# touch_controller.net
KiCad netlist of a schematic drawn in EAGLE
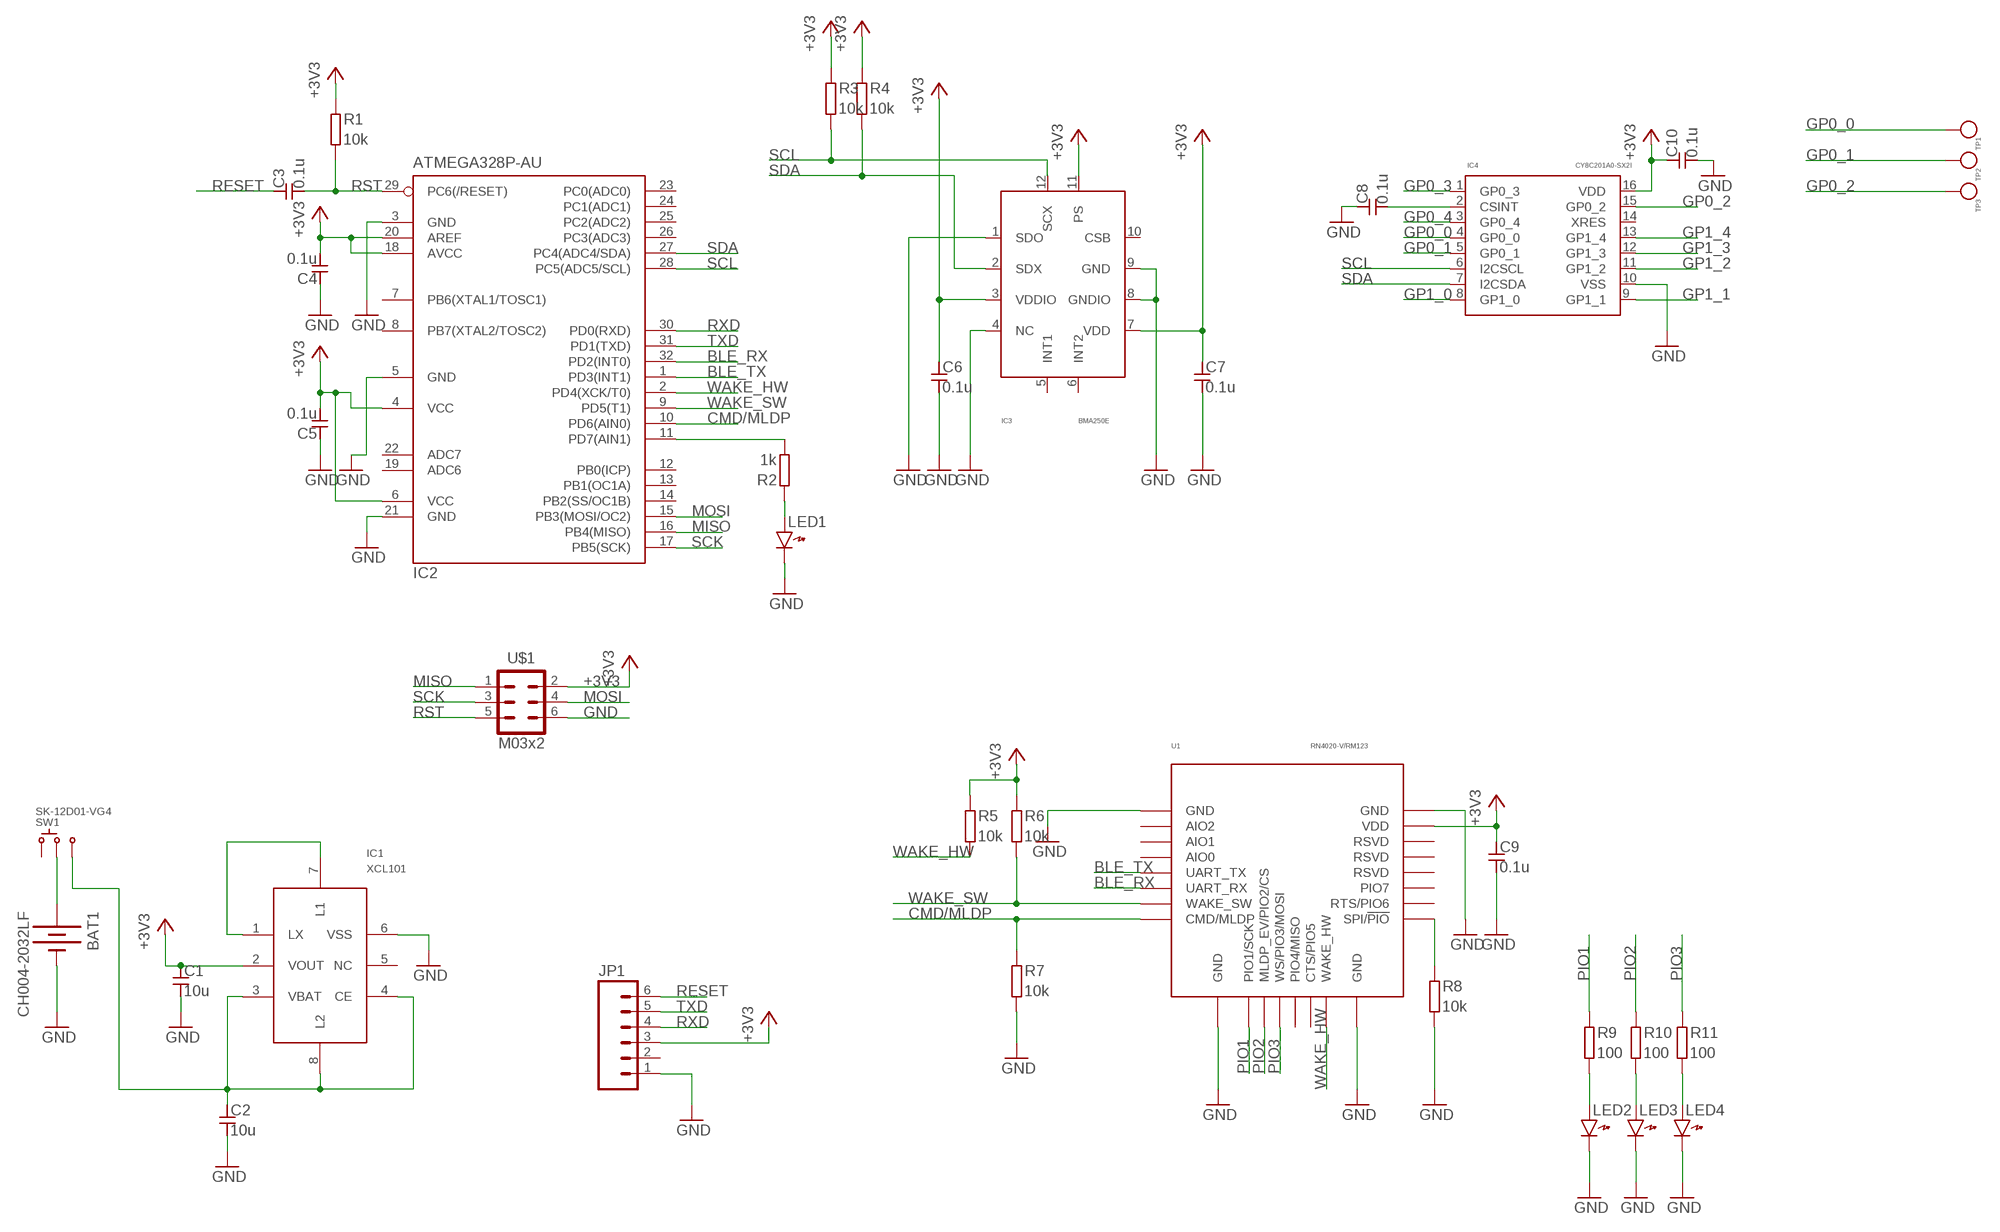
[diagram p0: schematic, sheet 1]

(export (version "E")
  (design (tool "Eeschema 10.0.6"))
  (components
    (comp (ref "BAT1")
      (value "CH004-2032LF")
      (footprint "eagle-import:CH004-2032LF")
      (libsource (lib "eagle-import") (part "CH004-2032LF"))
    )
    (comp (ref "C1")
      (value "10u")
      (footprint "eagle-import:SMD2012_REDUCED")
      (libsource (lib "eagle-import") (part "CAPACITOR2012_REDUCED"))
    )
    (comp (ref "C2")
      (value "10u")
      (footprint "eagle-import:SMD2012_REDUCED")
      (libsource (lib "eagle-import") (part "CAPACITOR2012_REDUCED"))
    )
    (comp (ref "C3")
      (value "0.1u")
      (footprint "eagle-import:SMD1608_REDUCED")
      (libsource (lib "eagle-import") (part "CAPACITOR1608_REDUCED"))
    )
    (comp (ref "C4")
      (value "0.1u")
      (footprint "eagle-import:SMD1608_REDUCED")
      (libsource (lib "eagle-import") (part "CAPACITOR1608_REDUCED"))
    )
    (comp (ref "C5")
      (value "0.1u")
      (footprint "eagle-import:SMD1608_REDUCED")
      (libsource (lib "eagle-import") (part "CAPACITOR1608_REDUCED"))
    )
    (comp (ref "C6")
      (value "0.1u")
      (footprint "eagle-import:SMD1608_REDUCED")
      (libsource (lib "eagle-import") (part "CAPACITOR1608_REDUCED"))
    )
    (comp (ref "C7")
      (value "0.1u")
      (footprint "eagle-import:SMD1608_REDUCED")
      (libsource (lib "eagle-import") (part "CAPACITOR1608_REDUCED"))
    )
    (comp (ref "C8")
      (value "0.1u")
      (footprint "eagle-import:SMD1608_REDUCED")
      (libsource (lib "eagle-import") (part "CAPACITOR1608_REDUCED"))
    )
    (comp (ref "C9")
      (value "0.1u")
      (footprint "eagle-import:SMD1608_REDUCED")
      (libsource (lib "eagle-import") (part "CAPACITOR1608_REDUCED"))
    )
    (comp (ref "C10")
      (value "0.1u")
      (footprint "eagle-import:SMD1608_REDUCED")
      (libsource (lib "eagle-import") (part "CAPACITOR1608_REDUCED"))
    )
    (comp (ref "IC1")
      (value "XCL101")
      (footprint "eagle-import:CL-2025")
      (libsource (lib "eagle-import") (part "XCL101"))
    )
    (comp (ref "IC2")
      (value "ATMEGA328P-AU")
      (footprint "eagle-import:TQFP32-08")
      (libsource (lib "eagle-import") (part "ATMEGA328P-AU"))
    )
    (comp (ref "IC3")
      (value "BMA250E")
      (footprint "eagle-import:LGA-12")
      (libsource (lib "eagle-import") (part "BMA250E"))
    )
    (comp (ref "IC4")
      (value "CY8C201A0-SX2I")
      (footprint "eagle-import:SOIC-16")
      (libsource (lib "eagle-import") (part "CY8C201A0-SX2I"))
    )
    (comp (ref "JP1")
      (value "M06NOSILK")
      (footprint "eagle-import:1X06-NOSILK")
      (libsource (lib "eagle-import") (part "M06NOSILK"))
    )
    (comp (ref "LED1")
      (value "LED1608_REDUCED")
      (footprint "eagle-import:LED1608_REDUCED")
      (libsource (lib "eagle-import") (part "LED1608_REDUCED"))
    )
    (comp (ref "LED2")
      (value "LED1608_REDUCED")
      (footprint "eagle-import:LED1608_REDUCED")
      (libsource (lib "eagle-import") (part "LED1608_REDUCED"))
    )
    (comp (ref "LED3")
      (value "LED1608_REDUCED")
      (footprint "eagle-import:LED1608_REDUCED")
      (libsource (lib "eagle-import") (part "LED1608_REDUCED"))
    )
    (comp (ref "LED4")
      (value "LED1608_REDUCED")
      (footprint "eagle-import:LED1608_REDUCED")
      (libsource (lib "eagle-import") (part "LED1608_REDUCED"))
    )
    (comp (ref "R1")
      (value "10k")
      (footprint "eagle-import:SMD1608_REDUCED")
      (libsource (lib "eagle-import") (part "RESISTOR1608_REDUCED"))
    )
    (comp (ref "R2")
      (value "1k")
      (footprint "eagle-import:SMD1608_REDUCED")
      (libsource (lib "eagle-import") (part "RESISTOR1608_REDUCED"))
    )
    (comp (ref "R3")
      (value "10k")
      (footprint "eagle-import:SMD1608_REDUCED")
      (libsource (lib "eagle-import") (part "RESISTOR1608_REDUCED"))
    )
    (comp (ref "R4")
      (value "10k")
      (footprint "eagle-import:SMD1608_REDUCED")
      (libsource (lib "eagle-import") (part "RESISTOR1608_REDUCED"))
    )
    (comp (ref "R5")
      (value "10k")
      (footprint "eagle-import:SMD1608_REDUCED")
      (libsource (lib "eagle-import") (part "RESISTOR1608_REDUCED"))
    )
    (comp (ref "R6")
      (value "10k")
      (footprint "eagle-import:SMD1608_REDUCED")
      (libsource (lib "eagle-import") (part "RESISTOR1608_REDUCED"))
    )
    (comp (ref "R7")
      (value "10k")
      (footprint "eagle-import:SMD1608_REDUCED")
      (libsource (lib "eagle-import") (part "RESISTOR1608_REDUCED"))
    )
    (comp (ref "R8")
      (value "10k")
      (footprint "eagle-import:SMD1608_REDUCED")
      (libsource (lib "eagle-import") (part "RESISTOR1608_REDUCED"))
    )
    (comp (ref "R9")
      (value "100")
      (footprint "eagle-import:SMD1608_REDUCED")
      (libsource (lib "eagle-import") (part "RESISTOR1608_REDUCED"))
    )
    (comp (ref "R10")
      (value "100")
      (footprint "eagle-import:SMD1608_REDUCED")
      (libsource (lib "eagle-import") (part "RESISTOR1608_REDUCED"))
    )
    (comp (ref "R11")
      (value "100")
      (footprint "eagle-import:SMD1608_REDUCED")
      (libsource (lib "eagle-import") (part "RESISTOR1608_REDUCED"))
    )
    (comp (ref "SW1")
      (value "SK-12D01-VG4")
      (footprint "eagle-import:SK-12D01-VG4")
      (libsource (lib "eagle-import") (part "SK-12D01-VG4"))
    )
    (comp (ref "TP1")
      (value "HT-0720-10")
      (footprint "eagle-import:HT-0720-10")
      (libsource (lib "eagle-import") (part "HT-0720-10"))
    )
    (comp (ref "TP2")
      (value "HT-0720-10")
      (footprint "eagle-import:HT-0720-10")
      (libsource (lib "eagle-import") (part "HT-0720-10"))
    )
    (comp (ref "TP3")
      (value "HT-0720-10")
      (footprint "eagle-import:HT-0720-10")
      (libsource (lib "eagle-import") (part "HT-0720-10"))
    )
    (comp (ref "U$1")
      (value "M03X2STD")
      (footprint "eagle-import:2X03")
      (libsource (lib "eagle-import") (part "M03X2STD"))
    )
    (comp (ref "U1")
      (value "RN4020-V/RM123")
      (footprint "eagle-import:RN4020")
      (libsource (lib "eagle-import") (part "RN4020-V/RM123"))
    )
  )
  (nets
    (net (code "1") (name "+3V3") (class "Default")
      (node (ref "C1") (pin "1") (pinfunction "1_1") (pintype "passive"))
      (node (ref "C10") (pin "1") (pinfunction "1_1") (pintype "passive"))
      (node (ref "C4") (pin "2") (pinfunction "2_2") (pintype "passive"))
      (node (ref "C5") (pin "2") (pinfunction "2_2") (pintype "passive"))
      (node (ref "C6") (pin "1") (pinfunction "1_1") (pintype "passive"))
      (node (ref "C7") (pin "1") (pinfunction "1_1") (pintype "passive"))
      (node (ref "C9") (pin "1") (pinfunction "1_1") (pintype "passive"))
      (node (ref "IC1") (pin "2") (pinfunction "VOUT_2") (pintype "bidirectional"))
      (node (ref "IC2") (pin "18") (pinfunction "AVCC_18") (pintype "power_in"))
      (node (ref "IC2") (pin "20") (pinfunction "AREF_20") (pintype "passive"))
      (node (ref "IC2") (pin "4") (pinfunction "VCC_4") (pintype "power_in"))
      (node (ref "IC2") (pin "6") (pinfunction "VCC_6") (pintype "power_in"))
      (node (ref "IC3") (pin "11") (pinfunction "PS_11") (pintype "bidirectional"))
      (node (ref "IC3") (pin "3") (pinfunction "VDDIO_3") (pintype "bidirectional"))
      (node (ref "IC3") (pin "7") (pinfunction "VDD_7") (pintype "bidirectional"))
      (node (ref "IC4") (pin "16") (pinfunction "VDD_16") (pintype "bidirectional"))
      (node (ref "JP1") (pin "3") (pinfunction "3_3") (pintype "passive"))
      (node (ref "R1") (pin "1") (pinfunction "1_1") (pintype "passive"))
      (node (ref "R3") (pin "1") (pinfunction "1_1") (pintype "passive"))
      (node (ref "R4") (pin "1") (pinfunction "1_1") (pintype "passive"))
      (node (ref "R5") (pin "1") (pinfunction "1_1") (pintype "passive"))
      (node (ref "R6") (pin "1") (pinfunction "1_1") (pintype "passive"))
      (node (ref "U$1") (pin "2") (pinfunction "2_2") (pintype "bidirectional"))
      (node (ref "U1") (pin "23") (pinfunction "VDD_23") (pintype "bidirectional"))
    )
    (net (code "2") (name "/BLE_RX") (class "Default")
      (node (ref "IC2") (pin "32") (pinfunction "PD2(INT0)_32") (pintype "bidirectional"))
      (node (ref "U1") (pin "6") (pinfunction "UART_RX_6") (pintype "bidirectional"))
    )
    (net (code "3") (name "/BLE_TX") (class "Default")
      (node (ref "IC2") (pin "1") (pinfunction "PD3(INT1)_1") (pintype "bidirectional"))
      (node (ref "U1") (pin "5") (pinfunction "UART_TX_5") (pintype "bidirectional"))
    )
    (net (code "4") (name "/CMD{slash}MLDP") (class "Default")
      (node (ref "IC2") (pin "10") (pinfunction "PD6(AIN0)_10") (pintype "bidirectional"))
      (node (ref "R7") (pin "1") (pinfunction "1_1") (pintype "passive"))
      (node (ref "U1") (pin "8") (pinfunction "CMD/MLDP_8") (pintype "bidirectional"))
    )
    (net (code "5") (name "/GP0_0") (class "Default")
      (node (ref "IC4") (pin "4") (pinfunction "GP0_0_4") (pintype "bidirectional"))
      (node (ref "TP1") (pin "P$1") (pinfunction "P$1_P$1") (pintype "bidirectional"))
    )
    (net (code "6") (name "/GP0_1") (class "Default")
      (node (ref "IC4") (pin "5") (pinfunction "GP0_1_5") (pintype "bidirectional"))
      (node (ref "TP2") (pin "P$1") (pinfunction "P$1_P$1") (pintype "bidirectional"))
    )
    (net (code "7") (name "/GP0_2") (class "Default")
      (node (ref "IC4") (pin "15") (pinfunction "GP0_2_15") (pintype "bidirectional"))
      (node (ref "TP3") (pin "P$1") (pinfunction "P$1_P$1") (pintype "bidirectional"))
    )
    (net (code "8") (name "/GP0_3") (class "Default")
      (node (ref "IC4") (pin "1") (pinfunction "GP0_3_1") (pintype "bidirectional"))
    )
    (net (code "9") (name "/GP0_4") (class "Default")
      (node (ref "IC4") (pin "3") (pinfunction "GP0_4_3") (pintype "bidirectional"))
    )
    (net (code "10") (name "/GP1_0") (class "Default")
      (node (ref "IC4") (pin "8") (pinfunction "GP1_0_8") (pintype "bidirectional"))
    )
    (net (code "11") (name "/GP1_1") (class "Default")
      (node (ref "IC4") (pin "9") (pinfunction "GP1_1_9") (pintype "bidirectional"))
    )
    (net (code "12") (name "/GP1_2") (class "Default")
      (node (ref "IC4") (pin "11") (pinfunction "GP1_2_11") (pintype "bidirectional"))
    )
    (net (code "13") (name "/GP1_3") (class "Default")
      (node (ref "IC4") (pin "12") (pinfunction "GP1_3_12") (pintype "bidirectional"))
    )
    (net (code "14") (name "/GP1_4") (class "Default")
      (node (ref "IC4") (pin "13") (pinfunction "GP1_4_13") (pintype "bidirectional"))
    )
    (net (code "15") (name "/MISO") (class "Default")
      (node (ref "IC2") (pin "16") (pinfunction "PB4(MISO)_16") (pintype "bidirectional"))
      (node (ref "U$1") (pin "1") (pinfunction "1_1") (pintype "bidirectional"))
    )
    (net (code "16") (name "/MOSI") (class "Default")
      (node (ref "IC2") (pin "15") (pinfunction "PB3(MOSI/OC2)_15") (pintype "bidirectional"))
      (node (ref "U$1") (pin "4") (pinfunction "4_4") (pintype "bidirectional"))
    )
    (net (code "17") (name "/PIO1") (class "Default")
      (node (ref "R9") (pin "1") (pinfunction "1_1") (pintype "passive"))
      (node (ref "U1") (pin "10") (pinfunction "PIO1/SCK_10") (pintype "bidirectional"))
    )
    (net (code "18") (name "/PIO2") (class "Default")
      (node (ref "R10") (pin "1") (pinfunction "1_1") (pintype "passive"))
      (node (ref "U1") (pin "11") (pinfunction "MLDP_EV/PIO2/CS_11") (pintype "bidirectional"))
    )
    (net (code "19") (name "/PIO3") (class "Default")
      (node (ref "R11") (pin "1") (pinfunction "1_1") (pintype "passive"))
      (node (ref "U1") (pin "12") (pinfunction "WS/PIO3/MOSI_12") (pintype "bidirectional"))
    )
    (net (code "20") (name "/RESET") (class "Default")
      (node (ref "C3") (pin "1") (pinfunction "1_1") (pintype "passive"))
      (node (ref "JP1") (pin "6") (pinfunction "6_6") (pintype "passive"))
    )
    (net (code "21") (name "/RST") (class "Default")
      (node (ref "C3") (pin "2") (pinfunction "2_2") (pintype "passive"))
      (node (ref "IC2") (pin "29") (pinfunction "PC6(/RESET)_29") (pintype "bidirectional"))
      (node (ref "R1") (pin "2") (pinfunction "2_2") (pintype "passive"))
      (node (ref "U$1") (pin "5") (pinfunction "5_5") (pintype "bidirectional"))
    )
    (net (code "22") (name "/RXD") (class "Default")
      (node (ref "IC2") (pin "30") (pinfunction "PD0(RXD)_30") (pintype "bidirectional"))
      (node (ref "JP1") (pin "4") (pinfunction "4_4") (pintype "passive"))
    )
    (net (code "23") (name "/SCK") (class "Default")
      (node (ref "IC2") (pin "17") (pinfunction "PB5(SCK)_17") (pintype "bidirectional"))
      (node (ref "U$1") (pin "3") (pinfunction "3_3") (pintype "bidirectional"))
    )
    (net (code "24") (name "/SCL") (class "Default")
      (node (ref "IC2") (pin "28") (pinfunction "PC5(ADC5/SCL)_28") (pintype "bidirectional"))
      (node (ref "IC3") (pin "12") (pinfunction "SCX_12") (pintype "bidirectional"))
      (node (ref "IC4") (pin "6") (pinfunction "I2CSCL_6") (pintype "bidirectional"))
      (node (ref "R3") (pin "2") (pinfunction "2_2") (pintype "passive"))
    )
    (net (code "25") (name "/SDA") (class "Default")
      (node (ref "IC2") (pin "27") (pinfunction "PC4(ADC4/SDA)_27") (pintype "bidirectional"))
      (node (ref "IC3") (pin "2") (pinfunction "SDX_2") (pintype "bidirectional"))
      (node (ref "IC4") (pin "7") (pinfunction "I2CSDA_7") (pintype "bidirectional"))
      (node (ref "R4") (pin "2") (pinfunction "2_2") (pintype "passive"))
    )
    (net (code "26") (name "/TXD") (class "Default")
      (node (ref "IC2") (pin "31") (pinfunction "PD1(TXD)_31") (pintype "bidirectional"))
      (node (ref "JP1") (pin "5") (pinfunction "5_5") (pintype "passive"))
    )
    (net (code "27") (name "/WAKE_HW") (class "Default")
      (node (ref "IC2") (pin "2") (pinfunction "PD4(XCK/T0)_2") (pintype "bidirectional"))
      (node (ref "R5") (pin "2") (pinfunction "2_2") (pintype "passive"))
      (node (ref "U1") (pin "15") (pinfunction "WAKE_HW_15") (pintype "bidirectional"))
    )
    (net (code "28") (name "/WAKE_SW") (class "Default")
      (node (ref "IC2") (pin "9") (pinfunction "PD5(T1)_9") (pintype "bidirectional"))
      (node (ref "R6") (pin "2") (pinfunction "2_2") (pintype "passive"))
      (node (ref "U1") (pin "7") (pinfunction "WAKE_SW_7") (pintype "bidirectional"))
    )
    (net (code "29") (name "GND") (class "Default")
      (node (ref "BAT1") (pin "-") (pinfunction "-_-") (pintype "power_in"))
      (node (ref "C1") (pin "2") (pinfunction "2_2") (pintype "passive"))
      (node (ref "C10") (pin "2") (pinfunction "2_2") (pintype "passive"))
      (node (ref "C2") (pin "2") (pinfunction "2_2") (pintype "passive"))
      (node (ref "C4") (pin "1") (pinfunction "1_1") (pintype "passive"))
      (node (ref "C5") (pin "1") (pinfunction "1_1") (pintype "passive"))
      (node (ref "C6") (pin "2") (pinfunction "2_2") (pintype "passive"))
      (node (ref "C7") (pin "2") (pinfunction "2_2") (pintype "passive"))
      (node (ref "C8") (pin "1") (pinfunction "1_1") (pintype "passive"))
      (node (ref "C9") (pin "2") (pinfunction "2_2") (pintype "passive"))
      (node (ref "IC1") (pin "6") (pinfunction "VSS_6") (pintype "bidirectional"))
      (node (ref "IC2") (pin "21") (pinfunction "GND_21") (pintype "power_in"))
      (node (ref "IC2") (pin "3") (pinfunction "GND_3") (pintype "power_in"))
      (node (ref "IC2") (pin "5") (pinfunction "GND_5") (pintype "power_in"))
      (node (ref "IC3") (pin "1") (pinfunction "SDO_1") (pintype "bidirectional"))
      (node (ref "IC3") (pin "4") (pinfunction "NC_4") (pintype "bidirectional"))
      (node (ref "IC3") (pin "8") (pinfunction "GNDIO_8") (pintype "bidirectional"))
      (node (ref "IC3") (pin "9") (pinfunction "GND_9") (pintype "bidirectional"))
      (node (ref "IC4") (pin "10") (pinfunction "VSS_10") (pintype "bidirectional"))
      (node (ref "JP1") (pin "1") (pinfunction "1_1") (pintype "passive"))
      (node (ref "LED1") (pin "K") (pinfunction "K_K") (pintype "passive"))
      (node (ref "LED2") (pin "K") (pinfunction "K_K") (pintype "passive"))
      (node (ref "LED3") (pin "K") (pinfunction "K_K") (pintype "passive"))
      (node (ref "LED4") (pin "K") (pinfunction "K_K") (pintype "passive"))
      (node (ref "R7") (pin "2") (pinfunction "2_2") (pintype "passive"))
      (node (ref "R8") (pin "2") (pinfunction "2_2") (pintype "passive"))
      (node (ref "U$1") (pin "6") (pinfunction "6_6") (pintype "bidirectional"))
      (node (ref "U1") (pin "1") (pinfunction "GND_1") (pintype "bidirectional"))
      (node (ref "U1") (pin "16") (pinfunction "GND_16") (pintype "bidirectional"))
      (node (ref "U1") (pin "24") (pinfunction "GND_24") (pintype "bidirectional"))
      (node (ref "U1") (pin "9") (pinfunction "GND_9") (pintype "bidirectional"))
    )
    (net (code "30") (name "Net-(IC1-CE)") (class "Default")
      (node (ref "C2") (pin "1") (pinfunction "1_1") (pintype "passive"))
      (node (ref "IC1") (pin "3") (pinfunction "VBAT_3") (pintype "bidirectional"))
      (node (ref "IC1") (pin "4") (pinfunction "CE_4") (pintype "bidirectional"))
      (node (ref "IC1") (pin "8") (pinfunction "L2_8") (pintype "bidirectional"))
      (node (ref "SW1") (pin "3") (pinfunction "P$3_3") (pintype "bidirectional"))
    )
    (net (code "31") (name "Net-(IC1-L1)") (class "Default")
      (node (ref "IC1") (pin "1") (pinfunction "LX_1") (pintype "bidirectional"))
      (node (ref "IC1") (pin "7") (pinfunction "L1_7") (pintype "bidirectional"))
    )
    (net (code "32") (name "Net-(IC2-PD7(AIN1))") (class "Default")
      (node (ref "IC2") (pin "11") (pinfunction "PD7(AIN1)_11") (pintype "bidirectional"))
      (node (ref "R2") (pin "2") (pinfunction "2_2") (pintype "passive"))
    )
    (net (code "33") (name "Net-(IC4-CSINT)") (class "Default")
      (node (ref "C8") (pin "2") (pinfunction "2_2") (pintype "passive"))
      (node (ref "IC4") (pin "2") (pinfunction "CSINT_2") (pintype "bidirectional"))
    )
    (net (code "34") (name "Net-(LED1-PadA)") (class "Default")
      (node (ref "LED1") (pin "A") (pinfunction "A_A") (pintype "passive"))
      (node (ref "R2") (pin "1") (pinfunction "1_1") (pintype "passive"))
    )
    (net (code "35") (name "Net-(LED2-PadA)") (class "Default")
      (node (ref "LED2") (pin "A") (pinfunction "A_A") (pintype "passive"))
      (node (ref "R9") (pin "2") (pinfunction "2_2") (pintype "passive"))
    )
    (net (code "36") (name "Net-(LED3-PadA)") (class "Default")
      (node (ref "LED3") (pin "A") (pinfunction "A_A") (pintype "passive"))
      (node (ref "R10") (pin "2") (pinfunction "2_2") (pintype "passive"))
    )
    (net (code "37") (name "Net-(LED4-PadA)") (class "Default")
      (node (ref "LED4") (pin "A") (pinfunction "A_A") (pintype "passive"))
      (node (ref "R11") (pin "2") (pinfunction "2_2") (pintype "passive"))
    )
    (net (code "38") (name "Net-(SW1-P$2)") (class "Default")
      (node (ref "BAT1") (pin "+") (pinfunction "+_+") (pintype "power_in"))
      (node (ref "SW1") (pin "2") (pinfunction "P$2_2") (pintype "bidirectional"))
    )
    (net (code "39") (name "Net-(U1-SPI{slash}~{PIO})") (class "Default")
      (node (ref "R8") (pin "1") (pinfunction "1_1") (pintype "passive"))
      (node (ref "U1") (pin "17") (pinfunction "SPI/~{PIO}_17") (pintype "bidirectional"))
    )
    (net (code "40") (name "unconnected-(IC1-NC-Pad5)") (class "Default")
      (node (ref "IC1") (pin "5") (pinfunction "NC_5") (pintype "bidirectional"))
    )
    (net (code "41") (name "unconnected-(IC2-ADC6-Pad19)") (class "Default")
      (node (ref "IC2") (pin "19") (pinfunction "ADC6_19") (pintype "input"))
    )
    (net (code "42") (name "unconnected-(IC2-ADC7-Pad22)") (class "Default")
      (node (ref "IC2") (pin "22") (pinfunction "ADC7_22") (pintype "input"))
    )
    (net (code "43") (name "unconnected-(IC2-PB0(ICP)-Pad12)") (class "Default")
      (node (ref "IC2") (pin "12") (pinfunction "PB0(ICP)_12") (pintype "bidirectional"))
    )
    (net (code "44") (name "unconnected-(IC2-PB1(OC1A)-Pad13)") (class "Default")
      (node (ref "IC2") (pin "13") (pinfunction "PB1(OC1A)_13") (pintype "bidirectional"))
    )
    (net (code "45") (name "unconnected-(IC2-PB2(SS{slash}OC1B)-Pad14)") (class "Default")
      (node (ref "IC2") (pin "14") (pinfunction "PB2(SS/OC1B)_14") (pintype "bidirectional"))
    )
    (net (code "46") (name "unconnected-(IC2-PB6(XTAL1{slash}TOSC1)-Pad7)") (class "Default")
      (node (ref "IC2") (pin "7") (pinfunction "PB6(XTAL1/TOSC1)_7") (pintype "bidirectional"))
    )
    (net (code "47") (name "unconnected-(IC2-PB7(XTAL2{slash}TOSC2)-Pad8)") (class "Default")
      (node (ref "IC2") (pin "8") (pinfunction "PB7(XTAL2/TOSC2)_8") (pintype "bidirectional"))
    )
    (net (code "48") (name "unconnected-(IC2-PC0(ADC0)-Pad23)") (class "Default")
      (node (ref "IC2") (pin "23") (pinfunction "PC0(ADC0)_23") (pintype "bidirectional"))
    )
    (net (code "49") (name "unconnected-(IC2-PC1(ADC1)-Pad24)") (class "Default")
      (node (ref "IC2") (pin "24") (pinfunction "PC1(ADC1)_24") (pintype "bidirectional"))
    )
    (net (code "50") (name "unconnected-(IC2-PC2(ADC2)-Pad25)") (class "Default")
      (node (ref "IC2") (pin "25") (pinfunction "PC2(ADC2)_25") (pintype "bidirectional"))
    )
    (net (code "51") (name "unconnected-(IC2-PC3(ADC3)-Pad26)") (class "Default")
      (node (ref "IC2") (pin "26") (pinfunction "PC3(ADC3)_26") (pintype "bidirectional"))
    )
    (net (code "52") (name "unconnected-(IC3-CSB-Pad10)") (class "Default")
      (node (ref "IC3") (pin "10") (pinfunction "CSB_10") (pintype "bidirectional"))
    )
    (net (code "53") (name "unconnected-(IC3-INT1-Pad5)") (class "Default")
      (node (ref "IC3") (pin "5") (pinfunction "INT1_5") (pintype "bidirectional"))
    )
    (net (code "54") (name "unconnected-(IC3-INT2-Pad6)") (class "Default")
      (node (ref "IC3") (pin "6") (pinfunction "INT2_6") (pintype "bidirectional"))
    )
    (net (code "55") (name "unconnected-(IC4-XRES-Pad14)") (class "Default")
      (node (ref "IC4") (pin "14") (pinfunction "XRES_14") (pintype "bidirectional"))
    )
    (net (code "56") (name "unconnected-(JP1-Pad2)") (class "Default")
      (node (ref "JP1") (pin "2") (pinfunction "2_2") (pintype "passive"))
    )
    (net (code "57") (name "unconnected-(SW1-P$1-Pad1)") (class "Default")
      (node (ref "SW1") (pin "1") (pinfunction "P$1_1") (pintype "bidirectional"))
    )
    (net (code "58") (name "unconnected-(U1-AIO0-Pad4)") (class "Default")
      (node (ref "U1") (pin "4") (pinfunction "AIO0_4") (pintype "bidirectional"))
    )
    (net (code "59") (name "unconnected-(U1-AIO1-Pad3)") (class "Default")
      (node (ref "U1") (pin "3") (pinfunction "AIO1_3") (pintype "bidirectional"))
    )
    (net (code "60") (name "unconnected-(U1-AIO2-Pad2)") (class "Default")
      (node (ref "U1") (pin "2") (pinfunction "AIO2_2") (pintype "bidirectional"))
    )
    (net (code "61") (name "unconnected-(U1-CTS{slash}PIO5-Pad14)") (class "Default")
      (node (ref "U1") (pin "14") (pinfunction "CTS/PIO5_14") (pintype "bidirectional"))
    )
    (net (code "62") (name "unconnected-(U1-PIO4{slash}MISO-Pad13)") (class "Default")
      (node (ref "U1") (pin "13") (pinfunction "PIO4/MISO_13") (pintype "bidirectional"))
    )
    (net (code "63") (name "unconnected-(U1-PIO7-Pad19)") (class "Default")
      (node (ref "U1") (pin "19") (pinfunction "PIO7_19") (pintype "bidirectional"))
    )
    (net (code "64") (name "unconnected-(U1-RSVD-Pad20)") (class "Default")
      (node (ref "U1") (pin "20") (pinfunction "RSVD_20") (pintype "bidirectional"))
    )
    (net (code "65") (name "unconnected-(U1-RSVD-Pad21)") (class "Default")
      (node (ref "U1") (pin "21") (pinfunction "RSVD_21") (pintype "bidirectional"))
    )
    (net (code "66") (name "unconnected-(U1-RSVD-Pad22)") (class "Default")
      (node (ref "U1") (pin "22") (pinfunction "RSVD_22") (pintype "bidirectional"))
    )
    (net (code "67") (name "unconnected-(U1-RTS{slash}PIO6-Pad18)") (class "Default")
      (node (ref "U1") (pin "18") (pinfunction "RTS/PIO6_18") (pintype "bidirectional"))
    )
  )
)
